# Cruvi_Pinheader.net
KiCad netlist of a schematic drawn in Altium Designer
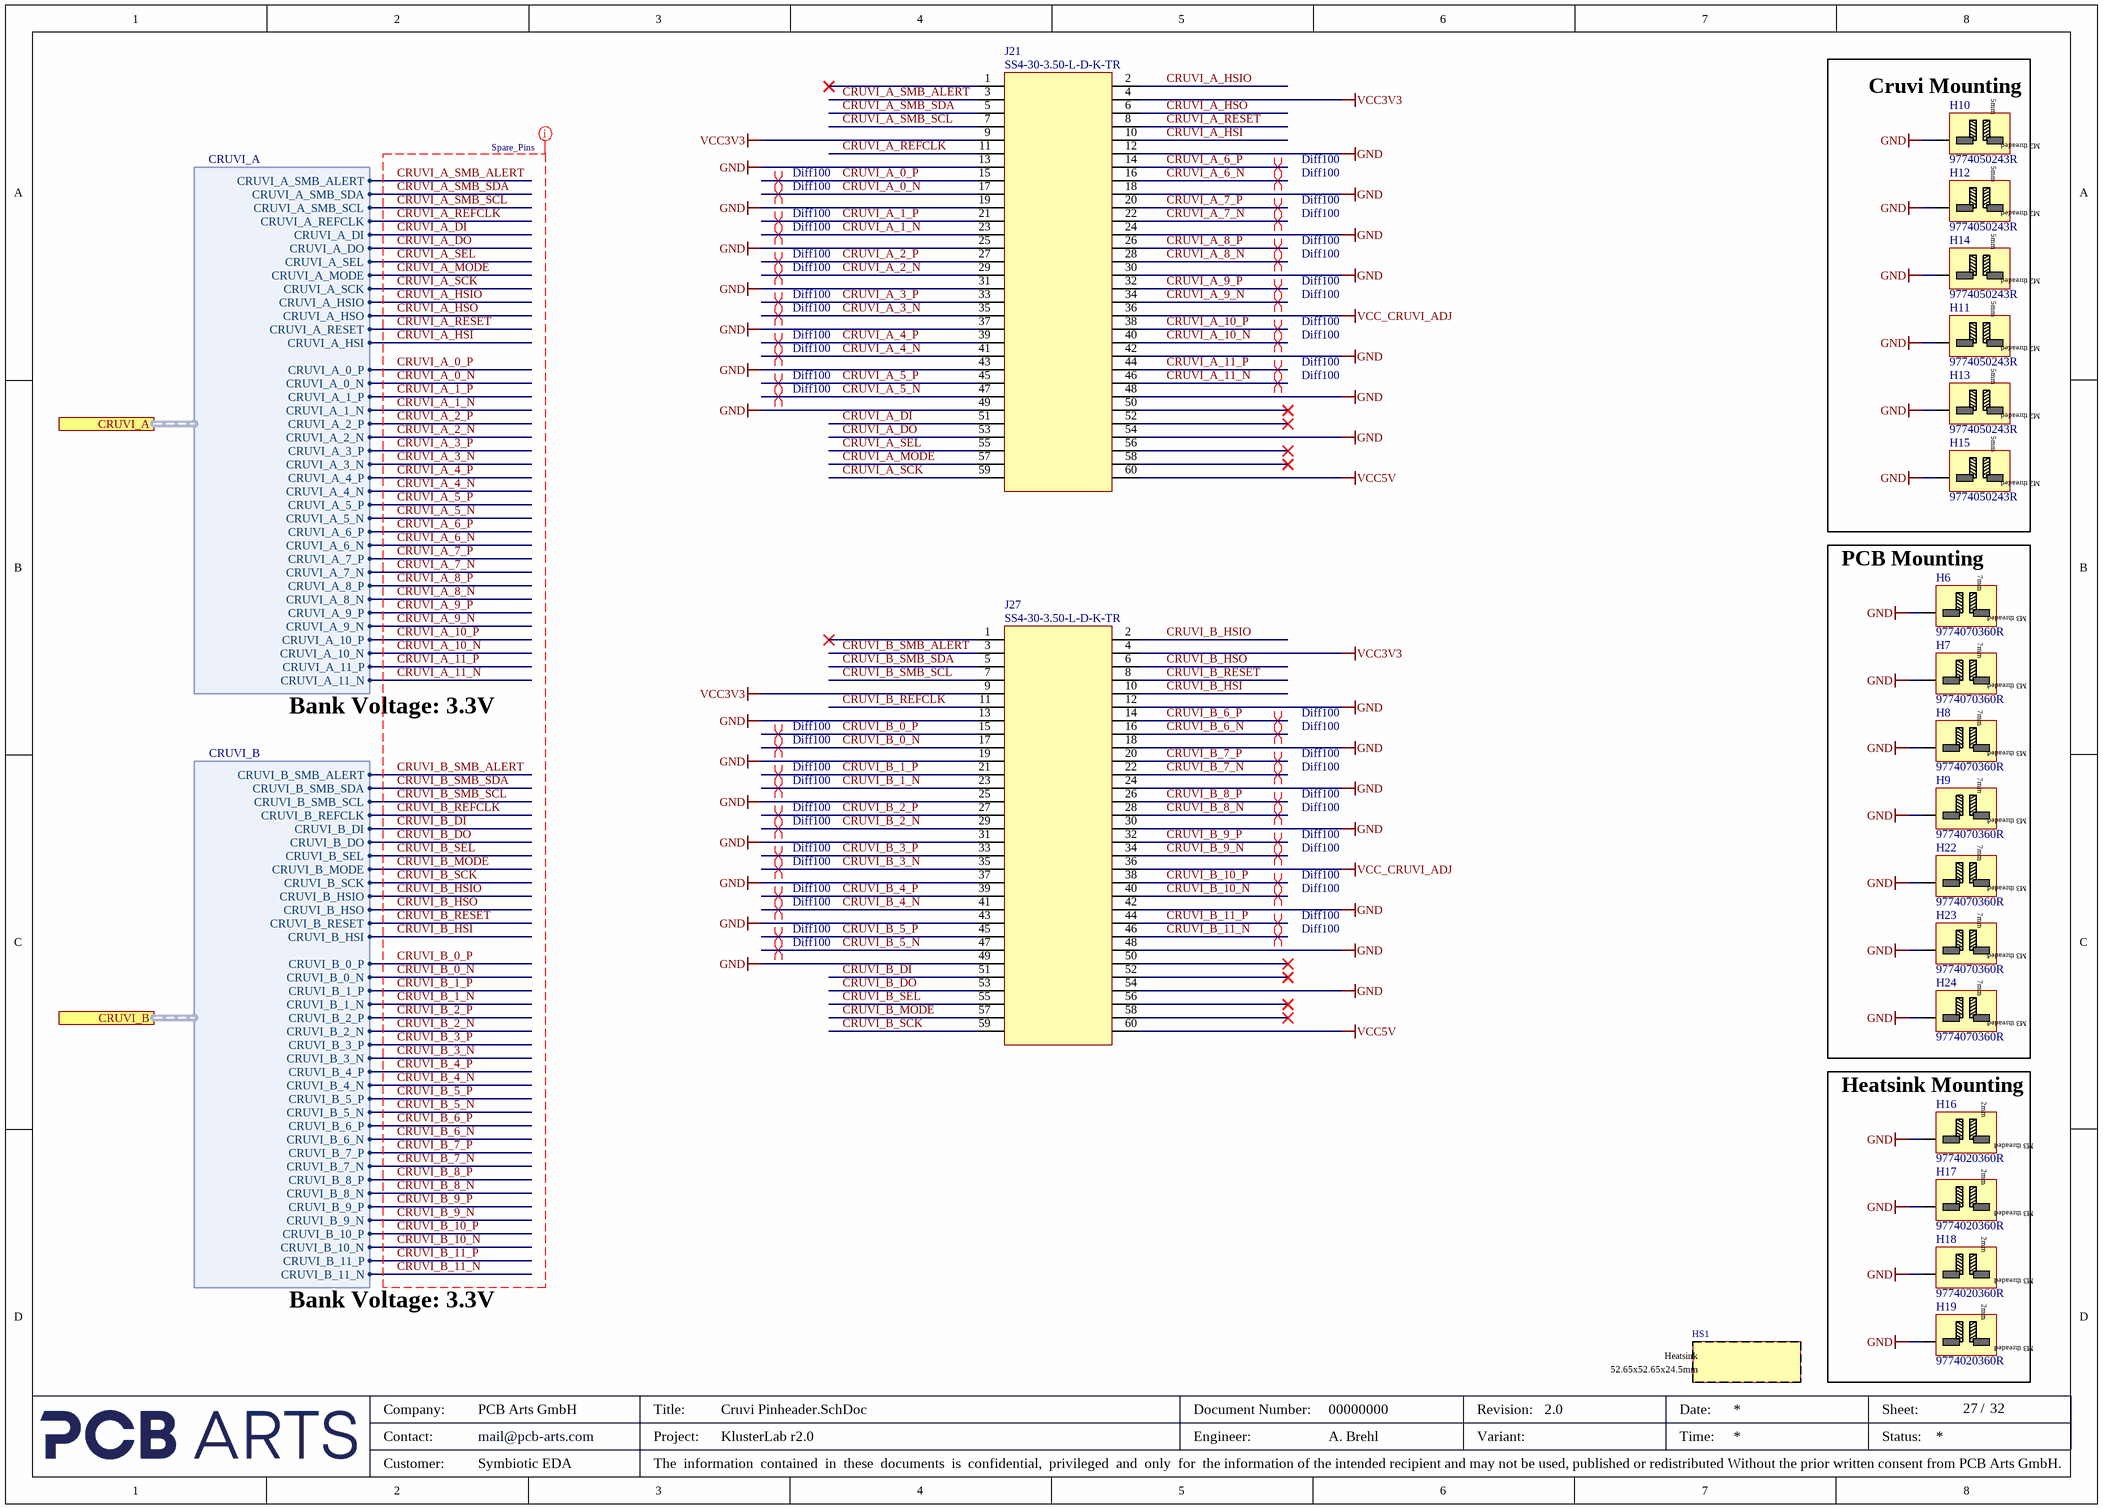
[diagram p0: Cruvi Pinheader.SchDoc]

(export (version "E")
  (design (tool "Eeschema 10.0.6"))
  (components
    (comp (ref "H6")
      (value "9774070360R")
      (footprint "Electro_Mech:9774070360R")
      (description "Würth Standoff M3 h:7mm 9774070360R")
      (libsource (lib "Electro_Mech") (part "Würth Standoff M3 h{colon}7mm"))
    )
    (comp (ref "H7")
      (value "9774070360R")
      (footprint "Electro_Mech:9774070360R")
      (description "Würth Standoff M3 h:7mm 9774070360R")
      (libsource (lib "Electro_Mech") (part "Würth Standoff M3 h{colon}7mm"))
    )
    (comp (ref "H8")
      (value "9774070360R")
      (footprint "Electro_Mech:9774070360R")
      (description "Würth Standoff M3 h:7mm 9774070360R")
      (libsource (lib "Electro_Mech") (part "Würth Standoff M3 h{colon}7mm"))
    )
    (comp (ref "H9")
      (value "9774070360R")
      (footprint "Electro_Mech:9774070360R")
      (description "Würth Standoff M3 h:7mm 9774070360R")
      (libsource (lib "Electro_Mech") (part "Würth Standoff M3 h{colon}7mm"))
    )
    (comp (ref "H10")
      (value "9774050243R")
      (footprint "Electro_Mech:9774050243R")
      (description "Würth Standoff M2 h:5mm 9774050243R")
      (libsource (lib "Electro_Mech") (part "Würth Standoff M2 h{colon}5mm"))
    )
    (comp (ref "H11")
      (value "9774050243R")
      (footprint "Electro_Mech:9774050243R")
      (description "Würth Standoff M2 h:5mm 9774050243R")
      (libsource (lib "Electro_Mech") (part "Würth Standoff M2 h{colon}5mm"))
    )
    (comp (ref "H12")
      (value "9774050243R")
      (footprint "Electro_Mech:9774050243R")
      (description "Würth Standoff M2 h:5mm 9774050243R")
      (libsource (lib "Electro_Mech") (part "Würth Standoff M2 h{colon}5mm"))
    )
    (comp (ref "H13")
      (value "9774050243R")
      (footprint "Electro_Mech:9774050243R")
      (description "Würth Standoff M2 h:5mm 9774050243R")
      (libsource (lib "Electro_Mech") (part "Würth Standoff M2 h{colon}5mm"))
    )
    (comp (ref "H14")
      (value "9774050243R")
      (footprint "Electro_Mech:9774050243R")
      (description "Würth Standoff M2 h:5mm 9774050243R")
      (libsource (lib "Electro_Mech") (part "Würth Standoff M2 h{colon}5mm"))
    )
    (comp (ref "H15")
      (value "9774050243R")
      (footprint "Electro_Mech:9774050243R")
      (description "Würth Standoff M2 h:5mm 9774050243R")
      (libsource (lib "Electro_Mech") (part "Würth Standoff M2 h{colon}5mm"))
    )
    (comp (ref "H16")
      (value "9774020360R")
      (footprint "Electro_Mech:9774020360R")
      (description "Würth Standoff M3 h:2mm 9774020360R")
      (libsource (lib "Electro_Mech") (part "Würth Standoff M3 h{colon}2mm"))
    )
    (comp (ref "H17")
      (value "9774020360R")
      (footprint "Electro_Mech:9774020360R")
      (description "Würth Standoff M3 h:2mm 9774020360R")
      (libsource (lib "Electro_Mech") (part "Würth Standoff M3 h{colon}2mm"))
    )
    (comp (ref "H18")
      (value "9774020360R")
      (footprint "Electro_Mech:9774020360R")
      (description "Würth Standoff M3 h:2mm 9774020360R")
      (libsource (lib "Electro_Mech") (part "Würth Standoff M3 h{colon}2mm"))
    )
    (comp (ref "H19")
      (value "9774020360R")
      (footprint "Electro_Mech:9774020360R")
      (description "Würth Standoff M3 h:2mm 9774020360R")
      (libsource (lib "Electro_Mech") (part "Würth Standoff M3 h{colon}2mm"))
    )
    (comp (ref "H22")
      (value "9774070360R")
      (footprint "Electro_Mech:9774070360R")
      (description "Würth Standoff M3 h:7mm 9774070360R")
      (libsource (lib "Electro_Mech") (part "Würth Standoff M3 h{colon}7mm"))
    )
    (comp (ref "H23")
      (value "9774070360R")
      (footprint "Electro_Mech:9774070360R")
      (description "Würth Standoff M3 h:7mm 9774070360R")
      (libsource (lib "Electro_Mech") (part "Würth Standoff M3 h{colon}7mm"))
    )
    (comp (ref "H24")
      (value "9774070360R")
      (footprint "Electro_Mech:9774070360R")
      (description "Würth Standoff M3 h:7mm 9774070360R")
      (libsource (lib "Electro_Mech") (part "Würth Standoff M3 h{colon}7mm"))
    )
    (comp (ref "HS1")
      (value "Heatsink Assembly 52.65x52.65x24.5mm")
      (footprint "Electro_Mech:ATS-61500W-C2-R0")
      (description "Machined Copper Heatsink for GaN Devices")
      (libsource (lib "Electro_Mech") (part "ATS-61500W-C2-R0_Heatsink Assembly 52.65x52.65x24.5mm"))
    )
    (comp (ref "J21")
      (value "SS4-30-3.50-L-D-K-TR")
      (footprint "SS4-30-3.50-L-D-K-TR")
      (description "Platine-zu-Platine & Mezzanine-Steckverbinder 0.40 mm Micro Blade & Beam Ultra Fine Pitch Socket")
      (libsource (lib "Conn") (part "SS4-30-3.50-L-D-K-TR"))
    )
    (comp (ref "J27")
      (value "SS4-30-3.50-L-D-K-TR")
      (footprint "SS4-30-3.50-L-D-K-TR")
      (description "Platine-zu-Platine & Mezzanine-Steckverbinder 0.40 mm Micro Blade & Beam Ultra Fine Pitch Socket")
      (libsource (lib "Conn") (part "SS4-30-3.50-L-D-K-TR"))
    )
  )
  (nets
    (net (code "3") (name "/CRUVI_A_0_N") (class "Default") (node (ref "J21") (pin "17") (pintype "passive")))
    (net (code "4") (name "/CRUVI_A_0_P") (class "Default") (node (ref "J21") (pin "15") (pintype "passive")))
    (net (code "5") (name "/CRUVI_A_1_N") (class "Default") (node (ref "J21") (pin "23") (pintype "passive")))
    (net (code "6") (name "/CRUVI_A_1_P") (class "Default") (node (ref "J21") (pin "21") (pintype "passive")))
    (net (code "7") (name "/CRUVI_A_2_N") (class "Default") (node (ref "J21") (pin "29") (pintype "passive")))
    (net (code "8") (name "/CRUVI_A_2_P") (class "Default") (node (ref "J21") (pin "27") (pintype "passive")))
    (net (code "9") (name "/CRUVI_A_3_N") (class "Default") (node (ref "J21") (pin "35") (pintype "passive")))
    (net (code "10") (name "/CRUVI_A_3_P") (class "Default")
      (node (ref "J21") (pin "33") (pintype "passive"))
    )
    (net (code "11") (name "/CRUVI_A_4_N") (class "Default")
      (node (ref "J21") (pin "41") (pintype "passive"))
    )
    (net (code "12") (name "/CRUVI_A_4_P") (class "Default")
      (node (ref "J21") (pin "39") (pintype "passive"))
    )
    (net (code "13") (name "/CRUVI_A_5_N") (class "Default")
      (node (ref "J21") (pin "47") (pintype "passive"))
    )
    (net (code "14") (name "/CRUVI_A_5_P") (class "Default")
      (node (ref "J21") (pin "45") (pintype "passive"))
    )
    (net (code "15") (name "/CRUVI_A_6_N") (class "Default")
      (node (ref "J21") (pin "16") (pintype "passive"))
    )
    (net (code "16") (name "/CRUVI_A_6_P") (class "Default")
      (node (ref "J21") (pin "14") (pintype "passive"))
    )
    (net (code "17") (name "/CRUVI_A_7_N") (class "Default")
      (node (ref "J21") (pin "22") (pintype "passive"))
    )
    (net (code "18") (name "/CRUVI_A_7_P") (class "Default")
      (node (ref "J21") (pin "20") (pintype "passive"))
    )
    (net (code "19") (name "/CRUVI_A_8_N") (class "Default")
      (node (ref "J21") (pin "28") (pintype "passive"))
    )
    (net (code "20") (name "/CRUVI_A_8_P") (class "Default")
      (node (ref "J21") (pin "26") (pintype "passive"))
    )
    (net (code "21") (name "/CRUVI_A_9_N") (class "Default")
      (node (ref "J21") (pin "34") (pintype "passive"))
    )
    (net (code "22") (name "/CRUVI_A_9_P") (class "Default")
      (node (ref "J21") (pin "32") (pintype "passive"))
    )
    (net (code "23") (name "/CRUVI_A_10_N") (class "Default")
      (node (ref "J21") (pin "40") (pintype "passive"))
    )
    (net (code "24") (name "/CRUVI_A_10_P") (class "Default")
      (node (ref "J21") (pin "38") (pintype "passive"))
    )
    (net (code "25") (name "/CRUVI_A_11_N") (class "Default")
      (node (ref "J21") (pin "46") (pintype "passive"))
    )
    (net (code "26") (name "/CRUVI_A_11_P") (class "Default")
      (node (ref "J21") (pin "44") (pintype "passive"))
    )
    (net (code "27") (name "/CRUVI_A_DI") (class "Default") (node (ref "J21") (pin "51") (pintype "passive")))
    (net (code "28") (name "/CRUVI_A_DO") (class "Default") (node (ref "J21") (pin "53") (pintype "passive")))
    (net (code "29") (name "/CRUVI_A_HSI") (class "Default")
      (node (ref "J21") (pin "10") (pintype "passive"))
    )
    (net (code "30") (name "/CRUVI_A_HSIO") (class "Default")
      (node (ref "J21") (pin "2") (pintype "passive"))
    )
    (net (code "31") (name "/CRUVI_A_HSO") (class "Default") (node (ref "J21") (pin "6") (pintype "passive")))
    (net (code "32") (name "/CRUVI_A_MODE") (class "Default")
      (node (ref "J21") (pin "57") (pintype "passive"))
    )
    (net (code "33") (name "/CRUVI_A_REFCLK") (class "Default")
      (node (ref "J21") (pin "11") (pintype "passive"))
    )
    (net (code "34") (name "/CRUVI_A_RESET") (class "Default")
      (node (ref "J21") (pin "8") (pintype "passive"))
    )
    (net (code "35") (name "/CRUVI_A_SCK") (class "Default")
      (node (ref "J21") (pin "59") (pintype "passive"))
    )
    (net (code "36") (name "/CRUVI_A_SEL") (class "Default")
      (node (ref "J21") (pin "55") (pintype "passive"))
    )
    (net (code "37") (name "/CRUVI_A_SMB_ALERT") (class "Default")
      (node (ref "J21") (pin "3") (pintype "passive"))
    )
    (net (code "38") (name "/CRUVI_A_SMB_SCL") (class "Default")
      (node (ref "J21") (pin "7") (pintype "passive"))
    )
    (net (code "39") (name "/CRUVI_A_SMB_SDA") (class "Default")
      (node (ref "J21") (pin "5") (pintype "passive"))
    )
    (net (code "40") (name "/CRUVI_B_0_N") (class "Default")
      (node (ref "J27") (pin "17") (pintype "passive"))
    )
    (net (code "41") (name "/CRUVI_B_0_P") (class "Default")
      (node (ref "J27") (pin "15") (pintype "passive"))
    )
    (net (code "42") (name "/CRUVI_B_1_N") (class "Default")
      (node (ref "J27") (pin "23") (pintype "passive"))
    )
    (net (code "43") (name "/CRUVI_B_1_P") (class "Default")
      (node (ref "J27") (pin "21") (pintype "passive"))
    )
    (net (code "44") (name "/CRUVI_B_2_N") (class "Default")
      (node (ref "J27") (pin "29") (pintype "passive"))
    )
    (net (code "45") (name "/CRUVI_B_2_P") (class "Default")
      (node (ref "J27") (pin "27") (pintype "passive"))
    )
    (net (code "46") (name "/CRUVI_B_3_N") (class "Default")
      (node (ref "J27") (pin "35") (pintype "passive"))
    )
    (net (code "47") (name "/CRUVI_B_3_P") (class "Default")
      (node (ref "J27") (pin "33") (pintype "passive"))
    )
    (net (code "48") (name "/CRUVI_B_4_N") (class "Default")
      (node (ref "J27") (pin "41") (pintype "passive"))
    )
    (net (code "49") (name "/CRUVI_B_4_P") (class "Default")
      (node (ref "J27") (pin "39") (pintype "passive"))
    )
    (net (code "50") (name "/CRUVI_B_5_N") (class "Default")
      (node (ref "J27") (pin "47") (pintype "passive"))
    )
    (net (code "51") (name "/CRUVI_B_5_P") (class "Default")
      (node (ref "J27") (pin "45") (pintype "passive"))
    )
    (net (code "52") (name "/CRUVI_B_6_N") (class "Default")
      (node (ref "J27") (pin "16") (pintype "passive"))
    )
    (net (code "53") (name "/CRUVI_B_6_P") (class "Default")
      (node (ref "J27") (pin "14") (pintype "passive"))
    )
    (net (code "54") (name "/CRUVI_B_7_N") (class "Default")
      (node (ref "J27") (pin "22") (pintype "passive"))
    )
    (net (code "55") (name "/CRUVI_B_7_P") (class "Default")
      (node (ref "J27") (pin "20") (pintype "passive"))
    )
    (net (code "56") (name "/CRUVI_B_8_N") (class "Default")
      (node (ref "J27") (pin "28") (pintype "passive"))
    )
    (net (code "57") (name "/CRUVI_B_8_P") (class "Default")
      (node (ref "J27") (pin "26") (pintype "passive"))
    )
    (net (code "58") (name "/CRUVI_B_9_N") (class "Default")
      (node (ref "J27") (pin "34") (pintype "passive"))
    )
    (net (code "59") (name "/CRUVI_B_9_P") (class "Default")
      (node (ref "J27") (pin "32") (pintype "passive"))
    )
    (net (code "60") (name "/CRUVI_B_10_N") (class "Default")
      (node (ref "J27") (pin "40") (pintype "passive"))
    )
    (net (code "61") (name "/CRUVI_B_10_P") (class "Default")
      (node (ref "J27") (pin "38") (pintype "passive"))
    )
    (net (code "62") (name "/CRUVI_B_11_N") (class "Default")
      (node (ref "J27") (pin "46") (pintype "passive"))
    )
    (net (code "63") (name "/CRUVI_B_11_P") (class "Default")
      (node (ref "J27") (pin "44") (pintype "passive"))
    )
    (net (code "64") (name "/CRUVI_B_DI") (class "Default") (node (ref "J27") (pin "51") (pintype "passive")))
    (net (code "65") (name "/CRUVI_B_DO") (class "Default") (node (ref "J27") (pin "53") (pintype "passive")))
    (net (code "66") (name "/CRUVI_B_HSI") (class "Default")
      (node (ref "J27") (pin "10") (pintype "passive"))
    )
    (net (code "67") (name "/CRUVI_B_HSIO") (class "Default")
      (node (ref "J27") (pin "2") (pintype "passive"))
    )
    (net (code "68") (name "/CRUVI_B_HSO") (class "Default") (node (ref "J27") (pin "6") (pintype "passive")))
    (net (code "69") (name "/CRUVI_B_MODE") (class "Default")
      (node (ref "J27") (pin "57") (pintype "passive"))
    )
    (net (code "70") (name "/CRUVI_B_REFCLK") (class "Default")
      (node (ref "J27") (pin "11") (pintype "passive"))
    )
    (net (code "71") (name "/CRUVI_B_RESET") (class "Default")
      (node (ref "J27") (pin "8") (pintype "passive"))
    )
    (net (code "72") (name "/CRUVI_B_SCK") (class "Default")
      (node (ref "J27") (pin "59") (pintype "passive"))
    )
    (net (code "73") (name "/CRUVI_B_SEL") (class "Default")
      (node (ref "J27") (pin "55") (pintype "passive"))
    )
    (net (code "74") (name "/CRUVI_B_SMB_ALERT") (class "Default")
      (node (ref "J27") (pin "3") (pintype "passive"))
    )
    (net (code "75") (name "/CRUVI_B_SMB_SCL") (class "Default")
      (node (ref "J27") (pin "7") (pintype "passive"))
    )
    (net (code "76") (name "/CRUVI_B_SMB_SDA") (class "Default")
      (node (ref "J27") (pin "5") (pintype "passive"))
    )
    (net (code "79") (name "GND") (class "Default")
      (node (ref "H10") (pin "1") (pinfunction "1_1") (pintype "passive"))
      (node (ref "H11") (pin "1") (pinfunction "1_1") (pintype "passive"))
      (node (ref "H12") (pin "1") (pinfunction "1_1") (pintype "passive"))
      (node (ref "H13") (pin "1") (pinfunction "1_1") (pintype "passive"))
      (node (ref "H14") (pin "1") (pinfunction "1_1") (pintype "passive"))
      (node (ref "H15") (pin "1") (pinfunction "1_1") (pintype "passive"))
      (node (ref "H16") (pin "1") (pinfunction "1_1") (pintype "passive"))
      (node (ref "H17") (pin "1") (pinfunction "1_1") (pintype "passive"))
      (node (ref "H18") (pin "1") (pinfunction "1_1") (pintype "passive"))
      (node (ref "H19") (pin "1") (pinfunction "1_1") (pintype "passive"))
      (node (ref "H22") (pin "1") (pinfunction "1_1") (pintype "passive"))
      (node (ref "H23") (pin "1") (pinfunction "1_1") (pintype "passive"))
      (node (ref "H24") (pin "1") (pinfunction "1_1") (pintype "passive"))
      (node (ref "H6") (pin "1") (pinfunction "1_1") (pintype "passive"))
      (node (ref "H7") (pin "1") (pinfunction "1_1") (pintype "passive"))
      (node (ref "H8") (pin "1") (pinfunction "1_1") (pintype "passive"))
      (node (ref "H9") (pin "1") (pinfunction "1_1") (pintype "passive"))
      (node (ref "J21") (pin "12") (pintype "passive"))
      (node (ref "J21") (pin "13") (pintype "passive"))
      (node (ref "J21") (pin "18") (pintype "passive"))
      (node (ref "J21") (pin "19") (pintype "passive"))
      (node (ref "J21") (pin "24") (pintype "passive"))
      (node (ref "J21") (pin "25") (pintype "passive"))
      (node (ref "J21") (pin "30") (pintype "passive"))
      (node (ref "J21") (pin "31") (pintype "passive"))
      (node (ref "J21") (pin "37") (pintype "passive"))
      (node (ref "J21") (pin "42") (pintype "passive"))
      (node (ref "J21") (pin "43") (pintype "passive"))
      (node (ref "J21") (pin "48") (pintype "passive"))
      (node (ref "J21") (pin "49") (pintype "passive"))
      (node (ref "J21") (pin "54") (pintype "passive"))
      (node (ref "J27") (pin "12") (pintype "passive"))
      (node (ref "J27") (pin "13") (pintype "passive"))
      (node (ref "J27") (pin "18") (pintype "passive"))
      (node (ref "J27") (pin "19") (pintype "passive"))
      (node (ref "J27") (pin "24") (pintype "passive"))
      (node (ref "J27") (pin "25") (pintype "passive"))
      (node (ref "J27") (pin "30") (pintype "passive"))
      (node (ref "J27") (pin "31") (pintype "passive"))
      (node (ref "J27") (pin "37") (pintype "passive"))
      (node (ref "J27") (pin "42") (pintype "passive"))
      (node (ref "J27") (pin "43") (pintype "passive"))
      (node (ref "J27") (pin "48") (pintype "passive"))
      (node (ref "J27") (pin "49") (pintype "passive"))
      (node (ref "J27") (pin "54") (pintype "passive"))
    )
    (net (code "80") (name "VCC3V3") (class "Default")
      (node (ref "J21") (pin "4") (pintype "passive"))
      (node (ref "J21") (pin "9") (pintype "passive"))
      (node (ref "J27") (pin "4") (pintype "passive"))
      (node (ref "J27") (pin "9") (pintype "passive"))
    )
    (net (code "81") (name "VCC5V") (class "Default")
      (node (ref "J21") (pin "60") (pintype "passive"))
      (node (ref "J27") (pin "60") (pintype "passive"))
    )
    (net (code "82") (name "VCC_CRUVI_ADJ") (class "Default")
      (node (ref "J21") (pin "36") (pintype "passive"))
      (node (ref "J27") (pin "36") (pintype "passive"))
    )
    (net (code "83") (name "unconnected-(J21-Pad1)") (class "Default")
      (node (ref "J21") (pin "1") (pintype "passive+no_connect"))
    )
    (net (code "84") (name "unconnected-(J21-Pad50)") (class "Default")
      (node (ref "J21") (pin "50") (pintype "passive+no_connect"))
    )
    (net (code "85") (name "unconnected-(J21-Pad52)") (class "Default")
      (node (ref "J21") (pin "52") (pintype "passive+no_connect"))
    )
    (net (code "86") (name "unconnected-(J21-Pad56)") (class "Default")
      (node (ref "J21") (pin "56") (pintype "passive+no_connect"))
    )
    (net (code "87") (name "unconnected-(J21-Pad58)") (class "Default")
      (node (ref "J21") (pin "58") (pintype "passive+no_connect"))
    )
    (net (code "88") (name "unconnected-(J27-Pad1)") (class "Default")
      (node (ref "J27") (pin "1") (pintype "passive+no_connect"))
    )
    (net (code "89") (name "unconnected-(J27-Pad50)") (class "Default")
      (node (ref "J27") (pin "50") (pintype "passive+no_connect"))
    )
    (net (code "90") (name "unconnected-(J27-Pad52)") (class "Default")
      (node (ref "J27") (pin "52") (pintype "passive+no_connect"))
    )
    (net (code "91") (name "unconnected-(J27-Pad56)") (class "Default")
      (node (ref "J27") (pin "56") (pintype "passive+no_connect"))
    )
    (net (code "92") (name "unconnected-(J27-Pad58)") (class "Default")
      (node (ref "J27") (pin "58") (pintype "passive+no_connect"))
    )
  )
)
